# CAN.net
KiCad netlist of a schematic drawn in Altium Designer
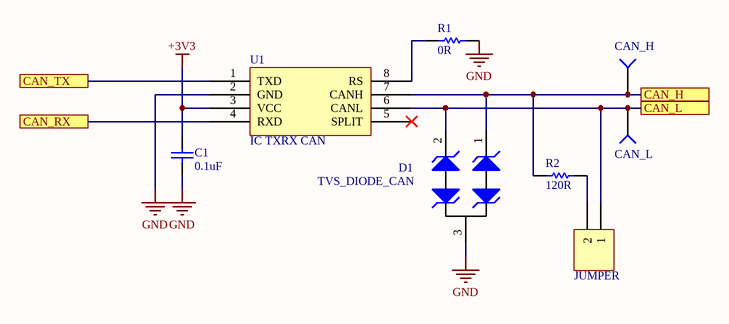
[diagram p0: CAN.SchDoc]

(export (version "E")
  (design (tool "Eeschema 10.0.6"))
  (components
    (comp (ref "1")
      (value "JUMPER")
      (footprint "HDR1X2")
      (description "Header, 2-Pin")
      (fields (field (name "PUBLISHER") "Altium Limited"))
      (libsource (lib "Miscellaneous Connectors") (part "Header 2"))
    )
    (comp (ref "C1")
      (value "0.1uF")
      (footprint "CAPC0603(1608)55_N")
      (description "CAP CER 0.1UF 16V X7R 0603")
      (fields (field (name "PART NUMBER") "CC0603KRX7R7BB104") (field (name "MANUFACTURER") "Yageo"))
      (libsource (lib "UWRT_Schematic_Library_2019") (part "CAP_0.1uF_16V_0603"))
    )
    (comp (ref "D1")
      (value "TVS_DIODE_CAN")
      (footprint "UWRT_Footprint_Library_2019:TVS_DIODE_CAN")
      (description "TVS DIODE 24V 41V SOT323-3")
      (fields (field (name "PART NUMBER") "PESD2CAN,215") (field (name "MANUFACTURER") "Nexperia USA Inc."))
      (libsource (lib "UWRT_Schematic_Library_2019") (part "TVS_DIODE_CAN"))
    )
    (comp (ref "R1")
      (value "0R")
      (footprint "RESC0603(1608)_N")
      (description "RES SMD 0 OHM JUMPER 1/10W 0603")
      (fields (field (name "MANUFACTURER") "Yageo") (field (name "Comment") "RES_0R_0603"))
      (libsource (lib "UWRT_Schematic_Library_2019") (part "RES_0R_0603"))
    )
    (comp (ref "R2")
      (value "120R")
      (footprint "RESC0603(1608)_N")
      (description "RES SMD 120 OHM 5% 1/10W 0603")
      (fields (field (name "MANUFACTURER") "Yageo") (field (name "TOLERANCE") "5%"))
      (libsource (lib "UWRT_Schematic_Library_2019") (part "RES_120R_0603"))
    )
    (comp (ref "TP1")
      (value "CAN_H")
      (footprint "TESTPOINT")
      (libsource (lib "UWRT_Schematic_Library_2019") (part "TESTPOINT_SMD"))
    )
    (comp (ref "TP2")
      (value "CAN_L")
      (footprint "TESTPOINT")
      (libsource (lib "UWRT_Schematic_Library_2019") (part "TESTPOINT_SMD"))
    )
    (comp (ref "U1")
      (value "IC TXRX CAN")
      (footprint "LT-S8_N")
      (description "IC TXRX CAN 4MBPS 8SO")
      (fields
        (field (name "MANUFACTURER") "Linear Technologies")
        (field (name "PART NUMBER") "LTC2875IS8#PBF")
      )
      (libsource (lib "UWRT_Schematic_Library_2019") (part "LTC2875"))
    )
  )
  (nets
    (net (code "1") (name "+3V3") (class "Default")
      (node (ref "C1") (pin "2") (pinfunction "2_2") (pintype "passive"))
      (node (ref "U1") (pin "3") (pinfunction "VCC_3") (pintype "passive"))
    )
    (net (code "2") (name "/CAN_H") (class "Default")
      (node (ref "D1") (pin "1") (pinfunction "1_1") (pintype "passive"))
      (node (ref "R2") (pin "1") (pinfunction "1_1") (pintype "passive"))
      (node (ref "TP1") (pin "1") (pinfunction "=value_1") (pintype "passive"))
      (node (ref "U1") (pin "7") (pinfunction "CANH_7") (pintype "passive"))
    )
    (net (code "3") (name "/CAN_L") (class "Default")
      (node (ref "1") (pin "1") (pinfunction "1_1") (pintype "passive"))
      (node (ref "D1") (pin "2") (pinfunction "2_2") (pintype "passive"))
      (node (ref "TP2") (pin "1") (pinfunction "=value_1") (pintype "passive"))
      (node (ref "U1") (pin "6") (pinfunction "CANL_6") (pintype "passive"))
    )
    (net (code "4") (name "/CAN_RX") (class "Default")
      (node (ref "U1") (pin "4") (pinfunction "RXD_4") (pintype "passive"))
    )
    (net (code "5") (name "/CAN_TX") (class "Default")
      (node (ref "U1") (pin "1") (pinfunction "TXD_1") (pintype "passive"))
    )
    (net (code "6") (name "GND") (class "Default")
      (node (ref "C1") (pin "1") (pinfunction "1_1") (pintype "passive"))
      (node (ref "D1") (pin "3") (pinfunction "3_3") (pintype "passive"))
      (node (ref "R1") (pin "2") (pinfunction "2_2") (pintype "passive"))
      (node (ref "U1") (pin "2") (pinfunction "GND_2") (pintype "passive"))
    )
    (net (code "7") (name "Net-(1-Pad2)") (class "Default")
      (node (ref "1") (pin "2") (pinfunction "2_2") (pintype "passive"))
      (node (ref "R2") (pin "2") (pinfunction "2_2") (pintype "passive"))
    )
    (net (code "8") (name "Net-(U1-RS)") (class "Default")
      (node (ref "R1") (pin "1") (pinfunction "1_1") (pintype "passive"))
      (node (ref "U1") (pin "8") (pinfunction "RS_8") (pintype "passive"))
    )
    (net (code "9") (name "unconnected-(U1-SPLIT-Pad5)") (class "Default")
      (node (ref "U1") (pin "5") (pinfunction "SPLIT_5") (pintype "passive+no_connect"))
    )
  )
)
